# OLED_Temp.net
KiCad netlist of a schematic drawn in EAGLE
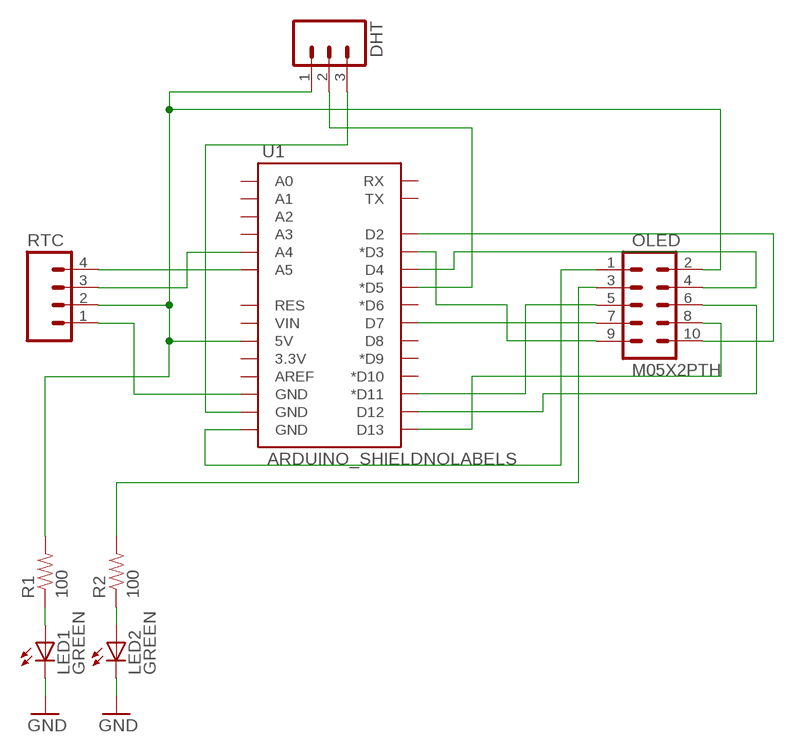
[diagram p0: schematic, sheet 1]

(export (version "E")
  (design (tool "Eeschema 10.0.6"))
  (components
    (comp (ref "DHT")
      (value "M03-SCREW-5MM")
      (footprint "eagle-import:SCREWTERMINAL-5MM-3")
      (libsource (lib "eagle-import") (part "M03-SCREW-5MM"))
    )
    (comp (ref "LED1")
      (value "GREEN")
      (footprint "eagle-import:LED5MM")
      (libsource (lib "eagle-import") (part "LED5MM"))
    )
    (comp (ref "LED2")
      (value "GREEN")
      (footprint "eagle-import:LED5MM")
      (libsource (lib "eagle-import") (part "LED5MM"))
    )
    (comp (ref "OLED")
      (value "M05X2PTH")
      (footprint "eagle-import:AVR_ICSP")
      (libsource (lib "eagle-import") (part "M05X2PTH"))
    )
    (comp (ref "R1")
      (value "100")
      (footprint "eagle-import:AXIAL-0.4")
      (libsource (lib "eagle-import") (part "RESISTORPTH-1/4W"))
    )
    (comp (ref "R2")
      (value "100")
      (footprint "eagle-import:AXIAL-0.4")
      (libsource (lib "eagle-import") (part "RESISTORPTH-1/4W"))
    )
    (comp (ref "RTC")
      (value "M04PTH")
      (footprint "eagle-import:1X04")
      (libsource (lib "eagle-import") (part "M04PTH"))
    )
    (comp (ref "U1")
      (value "ARDUINO_SHIELDNOLABELS")
      (footprint "eagle-import:DUEMILANOVE_SHIELD_NOLABELS")
      (libsource (lib "eagle-import") (part "ARDUINO_SHIELDNOLABELS"))
    )
  )
  (nets
    (net (code "1") (name "GND") (class "Default")
      (node (ref "LED1") (pin "K") (pinfunction "C_K") (pintype "passive"))
      (node (ref "LED2") (pin "K") (pinfunction "C_K") (pintype "passive"))
    )
    (net (code "2") (name "Net-(DHT-Pad3)") (class "Default")
      (node (ref "DHT") (pin "3") (pinfunction "3_3") (pintype "passive"))
      (node (ref "U1") (pin "GND@1") (pinfunction "GND_GND@1") (pintype "bidirectional"))
    )
    (net (code "3") (name "Net-(OLED-Pad1)") (class "Default")
      (node (ref "OLED") (pin "1") (pinfunction "1_1") (pintype "passive"))
      (node (ref "U1") (pin "GND@0") (pinfunction "GND_GND@0") (pintype "bidirectional"))
    )
    (net (code "4") (name "Net-(OLED-Pad4)") (class "Default")
      (node (ref "OLED") (pin "4") (pinfunction "4_4") (pintype "passive"))
      (node (ref "U1") (pin "D4") (pinfunction "D4_D4") (pintype "bidirectional"))
    )
    (net (code "5") (name "Net-(OLED-Pad6)") (class "Default")
      (node (ref "OLED") (pin "6") (pinfunction "6_6") (pintype "passive"))
      (node (ref "U1") (pin "D12") (pinfunction "D12_D12") (pintype "bidirectional"))
    )
    (net (code "6") (name "Net-(OLED-Pad7)") (class "Default")
      (node (ref "OLED") (pin "7") (pinfunction "7_7") (pintype "passive"))
      (node (ref "U1") (pin "D7") (pinfunction "D7_D7") (pintype "bidirectional"))
    )
    (net (code "7") (name "Net-(OLED-Pad8)") (class "Default")
      (node (ref "OLED") (pin "8") (pinfunction "8_8") (pintype "passive"))
      (node (ref "U1") (pin "D13") (pinfunction "D13_D13") (pintype "bidirectional"))
    )
    (net (code "8") (name "Net-(OLED-Pad10)") (class "Default")
      (node (ref "OLED") (pin "10") (pinfunction "10_10") (pintype "passive"))
      (node (ref "U1") (pin "D2") (pinfunction "D2_D2") (pintype "bidirectional"))
    )
    (net (code "9") (name "Net-(R1-1)") (class "Default")
      (node (ref "LED1") (pin "A") (pinfunction "A_A") (pintype "passive"))
      (node (ref "R1") (pin "P$1") (pinfunction "1_P$1") (pintype "passive"))
    )
    (net (code "10") (name "Net-(R1-2)") (class "Default")
      (node (ref "DHT") (pin "1") (pinfunction "1_1") (pintype "passive"))
      (node (ref "OLED") (pin "2") (pinfunction "2_2") (pintype "passive"))
      (node (ref "R1") (pin "P$2") (pinfunction "2_P$2") (pintype "passive"))
      (node (ref "RTC") (pin "2") (pinfunction "2_2") (pintype "passive"))
      (node (ref "U1") (pin "5V") (pinfunction "5V_5V") (pintype "bidirectional"))
    )
    (net (code "11") (name "Net-(R2-1)") (class "Default")
      (node (ref "LED2") (pin "A") (pinfunction "A_A") (pintype "passive"))
      (node (ref "R2") (pin "P$1") (pinfunction "1_P$1") (pintype "passive"))
    )
    (net (code "12") (name "Net-(R2-2)") (class "Default")
      (node (ref "OLED") (pin "3") (pinfunction "3_3") (pintype "passive"))
      (node (ref "R2") (pin "P$2") (pinfunction "2_P$2") (pintype "passive"))
    )
    (net (code "13") (name "Net-(RTC-Pad1)") (class "Default")
      (node (ref "RTC") (pin "1") (pinfunction "1_1") (pintype "passive"))
      (node (ref "U1") (pin "GND@2") (pinfunction "GND_GND@2") (pintype "bidirectional"))
    )
    (net (code "14") (name "Net-(RTC-Pad3)") (class "Default")
      (node (ref "RTC") (pin "3") (pinfunction "3_3") (pintype "passive"))
      (node (ref "U1") (pin "A4") (pinfunction "A4_A4") (pintype "bidirectional"))
    )
    (net (code "15") (name "Net-(RTC-Pad4)") (class "Default")
      (node (ref "RTC") (pin "4") (pinfunction "4_4") (pintype "passive"))
      (node (ref "U1") (pin "A5") (pinfunction "A5_A5") (pintype "bidirectional"))
    )
    (net (code "16") (name "Net-(U1-*D3)") (class "Default")
      (node (ref "OLED") (pin "9") (pinfunction "9_9") (pintype "passive"))
      (node (ref "U1") (pin "D3") (pinfunction "*D3_D3") (pintype "bidirectional"))
    )
    (net (code "17") (name "Net-(U1-*D5)") (class "Default")
      (node (ref "DHT") (pin "2") (pinfunction "2_2") (pintype "passive"))
      (node (ref "U1") (pin "D5") (pinfunction "*D5_D5") (pintype "bidirectional"))
    )
    (net (code "18") (name "Net-(U1-*D11)") (class "Default")
      (node (ref "OLED") (pin "5") (pinfunction "5_5") (pintype "passive"))
      (node (ref "U1") (pin "D11") (pinfunction "*D11_D11") (pintype "bidirectional"))
    )
    (net (code "19") (name "unconnected-(U1-*D6-PadD6)") (class "Default")
      (node (ref "U1") (pin "D6") (pinfunction "*D6_D6") (pintype "bidirectional"))
    )
    (net (code "20") (name "unconnected-(U1-*D9-PadD9)") (class "Default")
      (node (ref "U1") (pin "D9") (pinfunction "*D9_D9") (pintype "bidirectional"))
    )
    (net (code "21") (name "unconnected-(U1-*D10-PadD10)") (class "Default")
      (node (ref "U1") (pin "D10") (pinfunction "*D10_D10") (pintype "bidirectional"))
    )
    (net (code "22") (name "unconnected-(U1-Pad3.3V)") (class "Default")
      (node (ref "U1") (pin "3.3V") (pinfunction "3.3V_3.3V") (pintype "bidirectional"))
    )
    (net (code "23") (name "unconnected-(U1-PadA0)") (class "Default")
      (node (ref "U1") (pin "A0") (pinfunction "A0_A0") (pintype "bidirectional"))
    )
    (net (code "24") (name "unconnected-(U1-PadA1)") (class "Default")
      (node (ref "U1") (pin "A1") (pinfunction "A1_A1") (pintype "bidirectional"))
    )
    (net (code "25") (name "unconnected-(U1-PadA2)") (class "Default")
      (node (ref "U1") (pin "A2") (pinfunction "A2_A2") (pintype "bidirectional"))
    )
    (net (code "26") (name "unconnected-(U1-PadA3)") (class "Default")
      (node (ref "U1") (pin "A3") (pinfunction "A3_A3") (pintype "bidirectional"))
    )
    (net (code "27") (name "unconnected-(U1-PadAREF)") (class "Default")
      (node (ref "U1") (pin "AREF") (pinfunction "AREF_AREF") (pintype "bidirectional"))
    )
    (net (code "28") (name "unconnected-(U1-PadD8)") (class "Default")
      (node (ref "U1") (pin "D8") (pinfunction "D8_D8") (pintype "bidirectional"))
    )
    (net (code "29") (name "unconnected-(U1-PadRES)") (class "Default")
      (node (ref "U1") (pin "RES") (pinfunction "RES_RES") (pintype "bidirectional"))
    )
    (net (code "30") (name "unconnected-(U1-PadRX)") (class "Default")
      (node (ref "U1") (pin "RX") (pinfunction "RX_RX") (pintype "bidirectional"))
    )
    (net (code "31") (name "unconnected-(U1-PadTX)") (class "Default")
      (node (ref "U1") (pin "TX") (pinfunction "TX_TX") (pintype "bidirectional"))
    )
    (net (code "32") (name "unconnected-(U1-PadVIN)") (class "Default")
      (node (ref "U1") (pin "VIN") (pinfunction "VIN_VIN") (pintype "bidirectional"))
    )
  )
)
